# lcsc.net
KiCad netlist of a schematic drawn in EAGLE
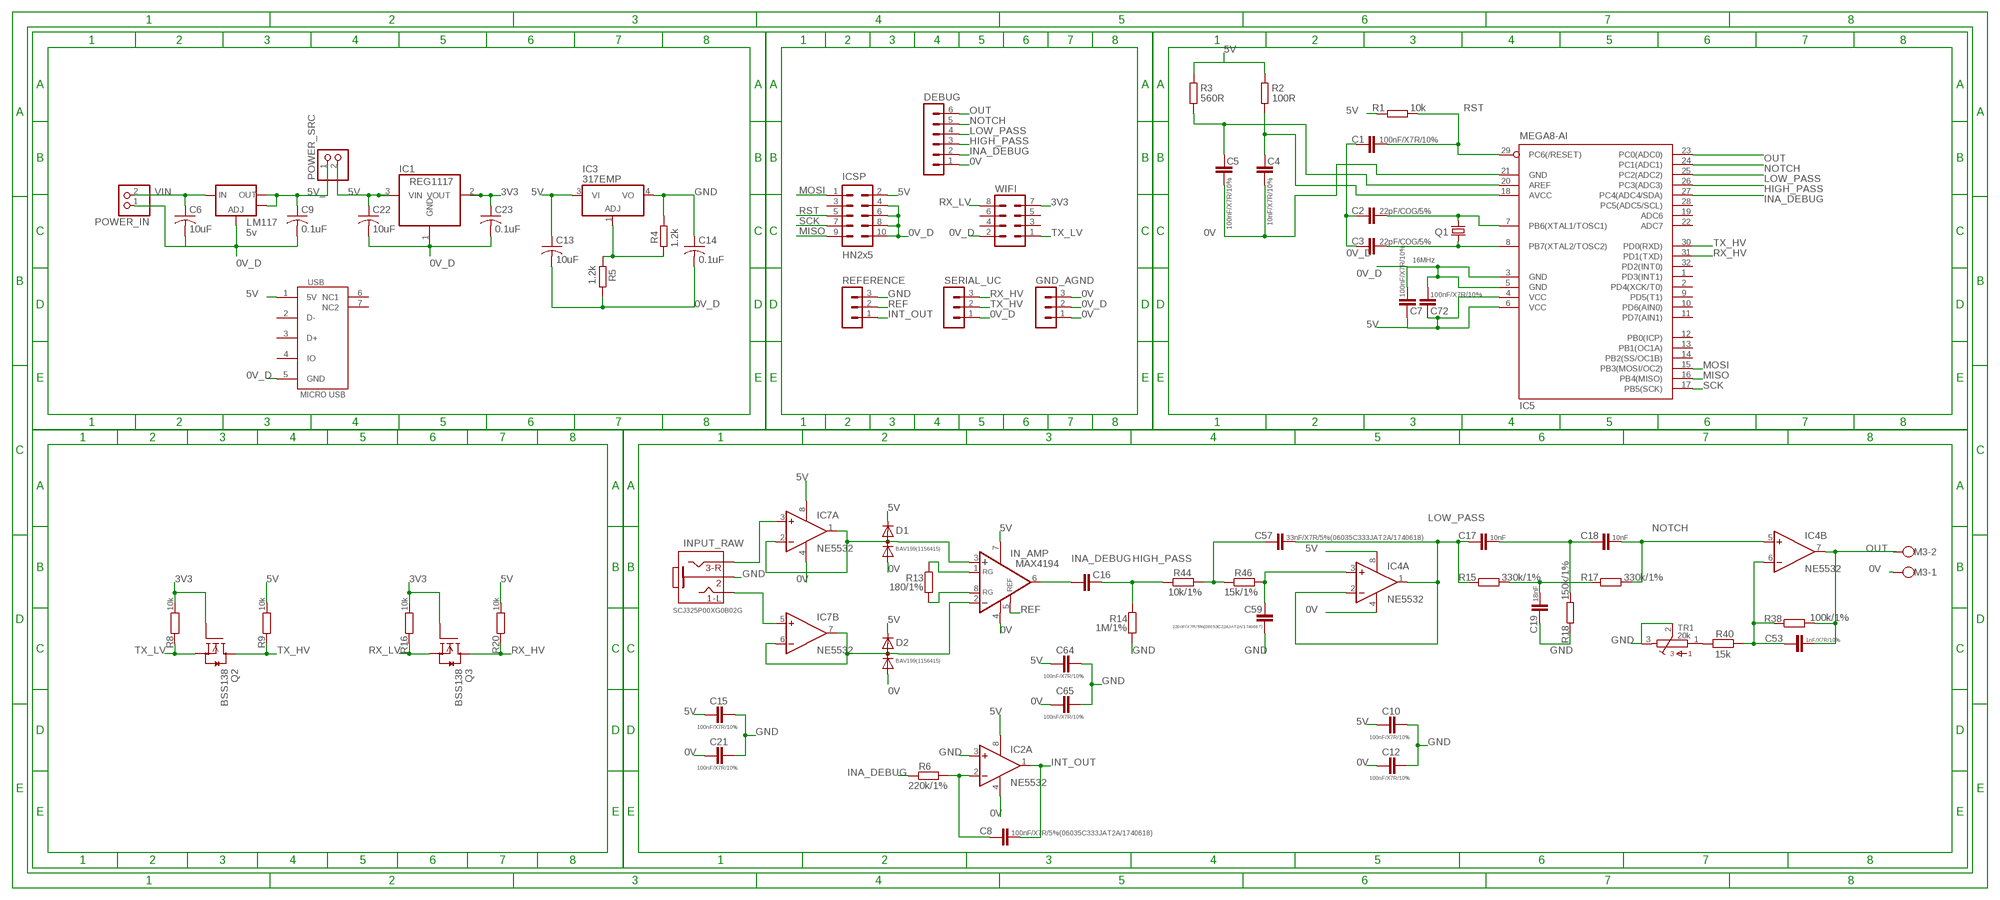
[diagram p0: schematic, sheet 1]

(export (version "E")
  (design (tool "Eeschema 10.0.6"))
  (components
    (comp (ref "C1")
      (value "100nF/X7R/10%")
      (footprint "eagle-import:C0603_DWS")
      (libsource (lib "eagle-import") (part "C-EUC0603_DWS"))
    )
    (comp (ref "C2")
      (value "22pF/COG/5%")
      (footprint "eagle-import:C0603_DWS")
      (libsource (lib "eagle-import") (part "C-EUC0603_DWS"))
    )
    (comp (ref "C3")
      (value "22pF/COG/5%")
      (footprint "eagle-import:C0603_DWS")
      (libsource (lib "eagle-import") (part "C-EUC0603_DWS"))
    )
    (comp (ref "C4")
      (value "10nF/X7R/10%")
      (footprint "eagle-import:C0603_DWS")
      (libsource (lib "eagle-import") (part "C-EUC0603_DWS"))
    )
    (comp (ref "C5")
      (value "100nF/X7R/10%")
      (footprint "eagle-import:C0603_DWS")
      (libsource (lib "eagle-import") (part "C-EUC0603_DWS"))
    )
    (comp (ref "C6")
      (value "10uF")
      (footprint "eagle-import:C0805")
      (libsource (lib "eagle-import") (part "C-USC0805"))
    )
    (comp (ref "C7")
      (value "100nF/X7R/10%")
      (footprint "eagle-import:C0603_DWS")
      (libsource (lib "eagle-import") (part "C-EUC0603_DWS"))
    )
    (comp (ref "C8")
      (value "100nF/X7R/5%(06035C333JAT2A/1740618)")
      (footprint "eagle-import:C0603_DWS")
      (libsource (lib "eagle-import") (part "C-EUC0603_DWS"))
    )
    (comp (ref "C9")
      (value "0.1uF")
      (footprint "eagle-import:C0805")
      (libsource (lib "eagle-import") (part "C-USC0805"))
    )
    (comp (ref "C10")
      (value "100nF/X7R/10%")
      (footprint "eagle-import:C0603_DWS")
      (libsource (lib "eagle-import") (part "C-EUC0603_DWS"))
    )
    (comp (ref "C12")
      (value "100nF/X7R/10%")
      (footprint "eagle-import:C0603_DWS")
      (libsource (lib "eagle-import") (part "C-EUC0603_DWS"))
    )
    (comp (ref "C13")
      (value "10uF")
      (footprint "eagle-import:C0805")
      (libsource (lib "eagle-import") (part "C-USC0805"))
    )
    (comp (ref "C14")
      (value "0.1uF")
      (footprint "eagle-import:C0805")
      (libsource (lib "eagle-import") (part "C-USC0805"))
    )
    (comp (ref "C15")
      (value "100nF/X7R/10%")
      (footprint "eagle-import:C0603_DWS")
      (libsource (lib "eagle-import") (part "C-EUC0603_DWS"))
    )
    (comp (ref "C16")
      (value "1uF/X5R/10%")
      (footprint "eagle-import:C0603_DWS")
      (libsource (lib "eagle-import") (part "C-EUC0603_DWS"))
    )
    (comp (ref "C17")
      (value "10nF")
      (footprint "eagle-import:C0603_DWS")
      (libsource (lib "eagle-import") (part "C-EUC0603_DWS"))
    )
    (comp (ref "C18")
      (value "10nF")
      (footprint "eagle-import:C0603_DWS")
      (libsource (lib "eagle-import") (part "C-EUC0603_DWS"))
    )
    (comp (ref "C19")
      (value "18nF")
      (footprint "eagle-import:C0603_DWS")
      (libsource (lib "eagle-import") (part "C-EUC0603_DWS"))
    )
    (comp (ref "C21")
      (value "100nF/X7R/10%")
      (footprint "eagle-import:C0603_DWS")
      (libsource (lib "eagle-import") (part "C-EUC0603_DWS"))
    )
    (comp (ref "C22")
      (value "10uF")
      (footprint "eagle-import:C0805")
      (libsource (lib "eagle-import") (part "C-USC0805"))
    )
    (comp (ref "C23")
      (value "0.1uF")
      (footprint "eagle-import:C0805")
      (libsource (lib "eagle-import") (part "C-USC0805"))
    )
    (comp (ref "C53")
      (value "1nF/X7R/10%")
      (footprint "eagle-import:C0603_DWS")
      (libsource (lib "eagle-import") (part "C-EUC0603_DWS"))
    )
    (comp (ref "C57")
      (value "33nF/X7R/5%(06035C333JAT2A/1740618)")
      (footprint "eagle-import:C0603_DWS")
      (libsource (lib "eagle-import") (part "C-EUC0603_DWS"))
    )
    (comp (ref "C59")
      (value "220nF/X7R/5%(08053C224JAT2A/1740667)")
      (footprint "eagle-import:C0805_5MIL_DWS")
      (libsource (lib "eagle-import") (part "C-EUC0805_5MIL_DWS"))
    )
    (comp (ref "C64")
      (value "100nF/X7R/10%")
      (footprint "eagle-import:C0603_DWS")
      (libsource (lib "eagle-import") (part "C-EUC0603_DWS"))
    )
    (comp (ref "C65")
      (value "100nF/X7R/10%")
      (footprint "eagle-import:C0603_DWS")
      (libsource (lib "eagle-import") (part "C-EUC0603_DWS"))
    )
    (comp (ref "C72")
      (value "100nF/X7R/10%")
      (footprint "eagle-import:C0603_DWS")
      (libsource (lib "eagle-import") (part "C-EUC0603_DWS"))
    )
    (comp (ref "D1")
      (value "BAV199(1156415)")
      (footprint "eagle-import:SOT23C(BAT54S)")
      (libsource (lib "eagle-import") (part "DIODE_AC-AC_"))
    )
    (comp (ref "D2")
      (value "BAV199(1156415)")
      (footprint "eagle-import:SOT23C(BAT54S)")
      (libsource (lib "eagle-import") (part "DIODE_AC-AC_"))
    )
    (comp (ref "DEBUG")
      (value "MA06-1")
      (footprint "eagle-import:MA06-1")
      (libsource (lib "eagle-import") (part "MA06-1"))
    )
    (comp (ref "GND_AGND")
      (value "MA03-1")
      (footprint "eagle-import:MA03-1")
      (libsource (lib "eagle-import") (part "MA03-1"))
    )
    (comp (ref "IC1")
      (value "REG1117")
      (footprint "eagle-import:SOT223")
      (libsource (lib "eagle-import") (part "REG1117"))
    )
    (comp (ref "IC2")
      (value "NE5532")
      (footprint "eagle-import:SO08")
      (libsource (lib "eagle-import") (part "LMV358?M"))
    )
    (comp (ref "IC3")
      (value "317EMP")
      (footprint "eagle-import:SOT223")
      (libsource (lib "eagle-import") (part "317EMP"))
    )
    (comp (ref "IC4")
      (value "NE5532")
      (footprint "eagle-import:SO08")
      (libsource (lib "eagle-import") (part "LMV358?M"))
    )
    (comp (ref "IC5")
      (value "MEGA8-AI")
      (footprint "eagle-import:TQFP32-08")
      (fields (field (name "MPN") "ATMEGA8-16AU"))
      (libsource (lib "eagle-import") (part "MEGA8-AI"))
    )
    (comp (ref "IC7")
      (value "NE5532")
      (footprint "eagle-import:SO08")
      (libsource (lib "eagle-import") (part "LMV358?M"))
    )
    (comp (ref "ICSP")
      (value "HN2x5")
      (footprint "eagle-import:ML10_NEW")
      (libsource (lib "eagle-import") (part "ML10ML10_NEW"))
    )
    (comp (ref "INPUT_RAW")
      (value "SCJ325P00XG0B02G")
      (footprint "eagle-import:PHONE_JACK-SMD")
      (libsource (lib "eagle-import") (part "JACK-3PINPHONE_JACK-SMD"))
    )
    (comp (ref "IN_AMP")
      (value "MAX4194")
      (footprint "eagle-import:SOIC8")
      (fields (field (name "MPN") "LT1168ACS8"))
      (libsource (lib "eagle-import") (part "LT1168S8AC"))
    )
    (comp (ref "LM117")
      (value "5v")
      (footprint "eagle-import:SOT223")
      (libsource (lib "eagle-import") (part "V_REG_LM1117SOT223"))
    )
    (comp (ref "M3")
      (value "W237-102")
      (footprint "eagle-import:W237-102")
      (fields (field (name "MPN") "237-102"))
      (libsource (lib "eagle-import") (part "W237-102"))
    )
    (comp (ref "POWER_IN")
      (value "PINHD-1X2")
      (footprint "eagle-import:1X02")
      (libsource (lib "eagle-import") (part "PINHD-1X2"))
    )
    (comp (ref "POWER_SRC")
      (value "PINHD-1X2")
      (footprint "eagle-import:1X02")
      (libsource (lib "eagle-import") (part "PINHD-1X2"))
    )
    (comp (ref "Q1")
      (value "16MHz")
      (footprint "eagle-import:HC49_SMD2_THIN")
      (libsource (lib "eagle-import") (part "HC49/S1"))
    )
    (comp (ref "Q2")
      (value "BSS138")
      (footprint "eagle-import:SOT23")
      (libsource (lib "eagle-import") (part "BSS138"))
    )
    (comp (ref "Q3")
      (value "BSS138")
      (footprint "eagle-import:SOT23")
      (libsource (lib "eagle-import") (part "BSS138"))
    )
    (comp (ref "R1")
      (value "10k")
      (footprint "eagle-import:R0603_5MIL_DWS")
      (libsource (lib "eagle-import") (part "R-EU_R0603_5MIL_DWS"))
    )
    (comp (ref "R2")
      (value "100R")
      (footprint "eagle-import:R0603_5MIL_DWS")
      (libsource (lib "eagle-import") (part "R-EU_R0603_5MIL_DWS"))
    )
    (comp (ref "R3")
      (value "560R")
      (footprint "eagle-import:R0603_5MIL_DWS")
      (libsource (lib "eagle-import") (part "R-EU_R0603_5MIL_DWS"))
    )
    (comp (ref "R4")
      (value "1.2k")
      (footprint "eagle-import:R0603_5MIL_DWS")
      (libsource (lib "eagle-import") (part "R-EU_R0603_5MIL_DWS"))
    )
    (comp (ref "R5")
      (value "1.2k")
      (footprint "eagle-import:R0603_5MIL_DWS")
      (libsource (lib "eagle-import") (part "R-EU_R0603_5MIL_DWS"))
    )
    (comp (ref "R6")
      (value "220k/1%")
      (footprint "eagle-import:R0603_5MIL_DWS")
      (libsource (lib "eagle-import") (part "R-EU_R0603_5MIL_DWS"))
    )
    (comp (ref "R8")
      (value "10k")
      (footprint "eagle-import:R0603_5MIL_DWS")
      (libsource (lib "eagle-import") (part "R-EU_R0603_5MIL_DWS"))
    )
    (comp (ref "R9")
      (value "10k")
      (footprint "eagle-import:R0603_5MIL_DWS")
      (libsource (lib "eagle-import") (part "R-EU_R0603_5MIL_DWS"))
    )
    (comp (ref "R13")
      (value "180/1%")
      (footprint "eagle-import:R0603_5MIL_DWS")
      (libsource (lib "eagle-import") (part "R-EU_R0603_5MIL_DWS"))
    )
    (comp (ref "R14")
      (value "1M/1%")
      (footprint "eagle-import:R0603_5MIL_DWS")
      (libsource (lib "eagle-import") (part "R-EU_R0603_5MIL_DWS"))
    )
    (comp (ref "R15")
      (value "330k/1%")
      (footprint "eagle-import:R0603_5MIL_DWS")
      (libsource (lib "eagle-import") (part "R-EU_R0603_5MIL_DWS"))
    )
    (comp (ref "R16")
      (value "10k")
      (footprint "eagle-import:R0603_5MIL_DWS")
      (libsource (lib "eagle-import") (part "R-EU_R0603_5MIL_DWS"))
    )
    (comp (ref "R17")
      (value "330k/1%")
      (footprint "eagle-import:R0603_5MIL_DWS")
      (libsource (lib "eagle-import") (part "R-EU_R0603_5MIL_DWS"))
    )
    (comp (ref "R18")
      (value "150k/1%")
      (footprint "eagle-import:R0603_5MIL_DWS")
      (libsource (lib "eagle-import") (part "R-EU_R0603_5MIL_DWS"))
    )
    (comp (ref "R20")
      (value "10k")
      (footprint "eagle-import:R0603_5MIL_DWS")
      (libsource (lib "eagle-import") (part "R-EU_R0603_5MIL_DWS"))
    )
    (comp (ref "R38")
      (value "100k/1%")
      (footprint "eagle-import:R0603_5MIL_DWS")
      (libsource (lib "eagle-import") (part "R-EU_R0603_5MIL_DWS"))
    )
    (comp (ref "R40")
      (value "15k")
      (footprint "eagle-import:R0603_5MIL_DWS")
      (libsource (lib "eagle-import") (part "R-EU_R0603_5MIL_DWS"))
    )
    (comp (ref "R44")
      (value "10k/1%")
      (footprint "eagle-import:R0603_5MIL_DWS")
      (libsource (lib "eagle-import") (part "R-EU_R0603_5MIL_DWS"))
    )
    (comp (ref "R46")
      (value "15k/1%")
      (footprint "eagle-import:R0603_5MIL_DWS")
      (libsource (lib "eagle-import") (part "R-EU_R0603_5MIL_DWS"))
    )
    (comp (ref "REFERENCE")
      (value "MA03-1")
      (footprint "eagle-import:MA03-1")
      (libsource (lib "eagle-import") (part "MA03-1"))
    )
    (comp (ref "SERIAL_UC")
      (value "MA03-1")
      (footprint "eagle-import:MA03-1")
      (libsource (lib "eagle-import") (part "MA03-1"))
    )
    (comp (ref "TR1")
      (value "20k")
      (footprint "eagle-import:S64Y")
      (libsource (lib "eagle-import") (part "S64Y"))
    )
    (comp (ref "USB")
      (value "MICRO_USB")
      (footprint "eagle-import:MICRO_USB")
      (libsource (lib "eagle-import") (part "MICRO_USB"))
    )
    (comp (ref "WIFI")
      (value "MA04-2")
      (footprint "eagle-import:MA04-2")
      (libsource (lib "eagle-import") (part "MA04-2"))
    )
  )
  (nets
    (net (code "1") (name "/0V") (class "Default")
      (node (ref "C12") (pin "1") (pinfunction "1_1") (pintype "passive"))
      (node (ref "C21") (pin "1") (pinfunction "1_1") (pintype "passive"))
      (node (ref "C4") (pin "2") (pinfunction "2_2") (pintype "passive"))
      (node (ref "C5") (pin "2") (pinfunction "2_2") (pintype "passive"))
      (node (ref "C65") (pin "1") (pinfunction "1_1") (pintype "passive"))
      (node (ref "D1") (pin "1") (pinfunction "A_1") (pintype "passive"))
      (node (ref "D2") (pin "1") (pinfunction "A_1") (pintype "passive"))
      (node (ref "DEBUG") (pin "1") (pinfunction "1_1") (pintype "passive"))
      (node (ref "GND_AGND") (pin "1") (pinfunction "1_1") (pintype "passive"))
      (node (ref "GND_AGND") (pin "3") (pinfunction "3_3") (pintype "passive"))
      (node (ref "IC2") (pin "4") (pinfunction "V-_4") (pintype "power_in"))
      (node (ref "IC4") (pin "4") (pinfunction "V-_4") (pintype "power_in"))
      (node (ref "IC5") (pin "21") (pinfunction "GND_21") (pintype "power_in"))
      (node (ref "IC7") (pin "4") (pinfunction "V-_4") (pintype "power_in"))
      (node (ref "IN_AMP") (pin "4") (pinfunction "V-_4") (pintype "power_in"))
      (node (ref "M3") (pin "1") (pinfunction "KL_1") (pintype "passive"))
    )
    (net (code "2") (name "/0V_D") (class "Default")
      (node (ref "C1") (pin "2") (pinfunction "2_2") (pintype "passive"))
      (node (ref "C13") (pin "2") (pinfunction "2_2") (pintype "passive"))
      (node (ref "C14") (pin "2") (pinfunction "2_2") (pintype "passive"))
      (node (ref "C2") (pin "2") (pinfunction "2_2") (pintype "passive"))
      (node (ref "C22") (pin "2") (pinfunction "2_2") (pintype "passive"))
      (node (ref "C23") (pin "2") (pinfunction "2_2") (pintype "passive"))
      (node (ref "C3") (pin "2") (pinfunction "2_2") (pintype "passive"))
      (node (ref "C6") (pin "2") (pinfunction "2_2") (pintype "passive"))
      (node (ref "C7") (pin "2") (pinfunction "2_2") (pintype "passive"))
      (node (ref "C72") (pin "2") (pinfunction "2_2") (pintype "passive"))
      (node (ref "C9") (pin "2") (pinfunction "2_2") (pintype "passive"))
      (node (ref "GND_AGND") (pin "2") (pinfunction "2_2") (pintype "passive"))
      (node (ref "IC1") (pin "1") (pinfunction "GND_1") (pintype "power_in"))
      (node (ref "IC5") (pin "3") (pinfunction "GND_3") (pintype "power_in"))
      (node (ref "IC5") (pin "5") (pinfunction "GND_5") (pintype "power_in"))
      (node (ref "ICSP") (pin "10") (pinfunction "10_10") (pintype "passive"))
      (node (ref "ICSP") (pin "4") (pinfunction "4_4") (pintype "passive"))
      (node (ref "ICSP") (pin "6") (pinfunction "6_6") (pintype "passive"))
      (node (ref "ICSP") (pin "8") (pinfunction "8_8") (pintype "passive"))
      (node (ref "LM117") (pin "1") (pinfunction "ADJ_1") (pintype "input"))
      (node (ref "POWER_IN") (pin "1") (pinfunction "1_1") (pintype "passive"))
      (node (ref "R5") (pin "1") (pinfunction "1_1") (pintype "passive"))
      (node (ref "SERIAL_UC") (pin "1") (pinfunction "1_1") (pintype "passive"))
      (node (ref "USB") (pin "5") (pinfunction "GND_5") (pintype "bidirectional"))
      (node (ref "WIFI") (pin "2") (pinfunction "2_2") (pintype "passive"))
    )
    (net (code "3") (name "/3V3") (class "Default")
      (node (ref "C23") (pin "1") (pinfunction "1_1") (pintype "passive"))
      (node (ref "IC1") (pin "2") (pinfunction "VOUT_2") (pintype "output"))
      (node (ref "Q2") (pin "1") (pinfunction "G_1") (pintype "passive"))
      (node (ref "Q3") (pin "1") (pinfunction "G_1") (pintype "passive"))
      (node (ref "R16") (pin "2") (pinfunction "2_2") (pintype "passive"))
      (node (ref "R8") (pin "2") (pinfunction "2_2") (pintype "passive"))
      (node (ref "WIFI") (pin "7") (pinfunction "7_7") (pintype "passive"))
    )
    (net (code "4") (name "/5V") (class "Default")
      (node (ref "C10") (pin "1") (pinfunction "1_1") (pintype "passive"))
      (node (ref "C13") (pin "1") (pinfunction "1_1") (pintype "passive"))
      (node (ref "C15") (pin "1") (pinfunction "1_1") (pintype "passive"))
      (node (ref "C22") (pin "1") (pinfunction "1_1") (pintype "passive"))
      (node (ref "C64") (pin "1") (pinfunction "1_1") (pintype "passive"))
      (node (ref "C7") (pin "1") (pinfunction "1_1") (pintype "passive"))
      (node (ref "C72") (pin "1") (pinfunction "1_1") (pintype "passive"))
      (node (ref "D1") (pin "2") (pinfunction "K_2") (pintype "passive"))
      (node (ref "D2") (pin "2") (pinfunction "K_2") (pintype "passive"))
      (node (ref "IC1") (pin "3") (pinfunction "VIN_3") (pintype "input"))
      (node (ref "IC2") (pin "8") (pinfunction "V+_8") (pintype "power_in"))
      (node (ref "IC3") (pin "3") (pinfunction "VI_3") (pintype "input"))
      (node (ref "IC4") (pin "8") (pinfunction "V+_8") (pintype "power_in"))
      (node (ref "IC5") (pin "4") (pinfunction "VCC_4") (pintype "power_in"))
      (node (ref "IC5") (pin "6") (pinfunction "VCC_6") (pintype "power_in"))
      (node (ref "IC7") (pin "8") (pinfunction "V+_8") (pintype "power_in"))
      (node (ref "ICSP") (pin "2") (pinfunction "2_2") (pintype "passive"))
      (node (ref "IN_AMP") (pin "7") (pinfunction "V+_7") (pintype "power_in"))
      (node (ref "POWER_SRC") (pin "2") (pinfunction "2_2") (pintype "passive"))
      (node (ref "R1") (pin "1") (pinfunction "1_1") (pintype "passive"))
      (node (ref "R2") (pin "2") (pinfunction "2_2") (pintype "passive"))
      (node (ref "R20") (pin "2") (pinfunction "2_2") (pintype "passive"))
      (node (ref "R3") (pin "2") (pinfunction "2_2") (pintype "passive"))
      (node (ref "R9") (pin "2") (pinfunction "2_2") (pintype "passive"))
      (node (ref "USB") (pin "1") (pinfunction "5V_1") (pintype "bidirectional"))
    )
    (net (code "5") (name "/5V_") (class "Default")
      (node (ref "C9") (pin "1") (pinfunction "1_1") (pintype "passive"))
      (node (ref "LM117") (pin "2") (pinfunction "OUT_2") (pintype "output"))
      (node (ref "LM117") (pin "4") (pinfunction "OUT_4") (pintype "output"))
      (node (ref "POWER_SRC") (pin "1") (pinfunction "1_1") (pintype "passive"))
    )
    (net (code "6") (name "/GND") (class "Default")
      (node (ref "C10") (pin "2") (pinfunction "2_2") (pintype "passive"))
      (node (ref "C12") (pin "2") (pinfunction "2_2") (pintype "passive"))
      (node (ref "C14") (pin "1") (pinfunction "1_1") (pintype "passive"))
      (node (ref "C15") (pin "2") (pinfunction "2_2") (pintype "passive"))
      (node (ref "C19") (pin "1") (pinfunction "1_1") (pintype "passive"))
      (node (ref "C21") (pin "2") (pinfunction "2_2") (pintype "passive"))
      (node (ref "C59") (pin "2") (pinfunction "2_2") (pintype "passive"))
      (node (ref "C64") (pin "2") (pinfunction "2_2") (pintype "passive"))
      (node (ref "C65") (pin "2") (pinfunction "2_2") (pintype "passive"))
      (node (ref "IC2") (pin "3") (pinfunction "+IN_3") (pintype "input"))
      (node (ref "IC3") (pin "4") (pinfunction "VO_4") (pintype "passive"))
      (node (ref "INPUT_RAW") (pin "1") (pinfunction "2_1") (pintype "input"))
      (node (ref "R14") (pin "2") (pinfunction "2_2") (pintype "passive"))
      (node (ref "R18") (pin "1") (pinfunction "1_1") (pintype "passive"))
      (node (ref "R4") (pin "1") (pinfunction "1_1") (pintype "passive"))
      (node (ref "REFERENCE") (pin "3") (pinfunction "3_3") (pintype "passive"))
      (node (ref "TR1") (pin "2") (pinfunction "2_2") (pintype "passive"))
      (node (ref "TR1") (pin "3") (pinfunction "3_3") (pintype "passive"))
    )
    (net (code "7") (name "/HIGH_PASS") (class "Default")
      (node (ref "C16") (pin "2") (pinfunction "2_2") (pintype "passive"))
      (node (ref "DEBUG") (pin "3") (pinfunction "3_3") (pintype "passive"))
      (node (ref "IC5") (pin "26") (pinfunction "PC3(ADC3)_26") (pintype "bidirectional"))
      (node (ref "R14") (pin "1") (pinfunction "1_1") (pintype "passive"))
      (node (ref "R44") (pin "1") (pinfunction "1_1") (pintype "passive"))
    )
    (net (code "8") (name "/INA_DEBUG") (class "Default")
      (node (ref "C16") (pin "1") (pinfunction "1_1") (pintype "passive"))
      (node (ref "DEBUG") (pin "2") (pinfunction "2_2") (pintype "passive"))
      (node (ref "IC5") (pin "27") (pinfunction "PC4(ADC4/SDA)_27") (pintype "bidirectional"))
      (node (ref "IN_AMP") (pin "6") (pinfunction "OUT_6") (pintype "output"))
      (node (ref "R6") (pin "1") (pinfunction "1_1") (pintype "passive"))
    )
    (net (code "9") (name "/INT_OUT") (class "Default")
      (node (ref "C8") (pin "2") (pinfunction "2_2") (pintype "passive"))
      (node (ref "IC2") (pin "1") (pinfunction "OUT_1") (pintype "output"))
      (node (ref "REFERENCE") (pin "1") (pinfunction "1_1") (pintype "passive"))
    )
    (net (code "10") (name "/LOW_PASS") (class "Default")
      (node (ref "C17") (pin "1") (pinfunction "1_1") (pintype "passive"))
      (node (ref "C57") (pin "2") (pinfunction "2_2") (pintype "passive"))
      (node (ref "DEBUG") (pin "4") (pinfunction "4_4") (pintype "passive"))
      (node (ref "IC4") (pin "1") (pinfunction "OUT_1") (pintype "output"))
      (node (ref "IC4") (pin "2") (pinfunction "-IN_2") (pintype "input"))
      (node (ref "IC5") (pin "25") (pinfunction "PC2(ADC2)_25") (pintype "bidirectional"))
      (node (ref "R15") (pin "1") (pinfunction "1_1") (pintype "passive"))
    )
    (net (code "11") (name "/MISO") (class "Default")
      (node (ref "IC5") (pin "16") (pinfunction "PB4(MISO)_16") (pintype "bidirectional"))
      (node (ref "ICSP") (pin "9") (pinfunction "9_9") (pintype "passive"))
    )
    (net (code "12") (name "/MOSI") (class "Default")
      (node (ref "IC5") (pin "15") (pinfunction "PB3(MOSI/OC2)_15") (pintype "bidirectional"))
      (node (ref "ICSP") (pin "1") (pinfunction "1_1") (pintype "passive"))
    )
    (net (code "13") (name "/NOTCH") (class "Default")
      (node (ref "C18") (pin "2") (pinfunction "2_2") (pintype "passive"))
      (node (ref "DEBUG") (pin "5") (pinfunction "5_5") (pintype "passive"))
      (node (ref "IC4") (pin "5") (pinfunction "+IN_5") (pintype "input"))
      (node (ref "IC5") (pin "24") (pinfunction "PC1(ADC1)_24") (pintype "bidirectional"))
      (node (ref "R17") (pin "2") (pinfunction "2_2") (pintype "passive"))
    )
    (net (code "14") (name "/OUT") (class "Default")
      (node (ref "C53") (pin "2") (pinfunction "2_2") (pintype "passive"))
      (node (ref "DEBUG") (pin "6") (pinfunction "6_6") (pintype "passive"))
      (node (ref "IC4") (pin "7") (pinfunction "OUT_7") (pintype "output"))
      (node (ref "IC5") (pin "23") (pinfunction "PC0(ADC0)_23") (pintype "bidirectional"))
      (node (ref "M3") (pin "2") (pinfunction "KL_2") (pintype "passive"))
      (node (ref "R38") (pin "2") (pinfunction "2_2") (pintype "passive"))
    )
    (net (code "15") (name "/REF") (class "Default")
      (node (ref "IN_AMP") (pin "5") (pinfunction "REF_5") (pintype "input"))
      (node (ref "REFERENCE") (pin "2") (pinfunction "2_2") (pintype "passive"))
    )
    (net (code "16") (name "/RST") (class "Default")
      (node (ref "C1") (pin "1") (pinfunction "1_1") (pintype "passive"))
      (node (ref "IC5") (pin "29") (pinfunction "PC6(/RESET)_29") (pintype "bidirectional"))
      (node (ref "ICSP") (pin "5") (pinfunction "5_5") (pintype "passive"))
      (node (ref "R1") (pin "2") (pinfunction "2_2") (pintype "passive"))
    )
    (net (code "17") (name "/RX_HV") (class "Default")
      (node (ref "IC5") (pin "31") (pinfunction "PD1(TXD)_31") (pintype "bidirectional"))
      (node (ref "Q3") (pin "3") (pinfunction "D_3") (pintype "passive"))
      (node (ref "R20") (pin "1") (pinfunction "1_1") (pintype "passive"))
      (node (ref "SERIAL_UC") (pin "3") (pinfunction "3_3") (pintype "passive"))
    )
    (net (code "18") (name "/RX_LV") (class "Default")
      (node (ref "Q3") (pin "2") (pinfunction "S_2") (pintype "passive"))
      (node (ref "R16") (pin "1") (pinfunction "1_1") (pintype "passive"))
      (node (ref "WIFI") (pin "8") (pinfunction "8_8") (pintype "passive"))
    )
    (net (code "19") (name "/SCK") (class "Default")
      (node (ref "IC5") (pin "17") (pinfunction "PB5(SCK)_17") (pintype "bidirectional"))
      (node (ref "ICSP") (pin "7") (pinfunction "7_7") (pintype "passive"))
    )
    (net (code "20") (name "/TX_HV") (class "Default")
      (node (ref "IC5") (pin "30") (pinfunction "PD0(RXD)_30") (pintype "bidirectional"))
      (node (ref "Q2") (pin "3") (pinfunction "D_3") (pintype "passive"))
      (node (ref "R9") (pin "1") (pinfunction "1_1") (pintype "passive"))
      (node (ref "SERIAL_UC") (pin "2") (pinfunction "2_2") (pintype "passive"))
    )
    (net (code "21") (name "/TX_LV") (class "Default")
      (node (ref "Q2") (pin "2") (pinfunction "S_2") (pintype "passive"))
      (node (ref "R8") (pin "1") (pinfunction "1_1") (pintype "passive"))
      (node (ref "WIFI") (pin "1") (pinfunction "1_1") (pintype "passive"))
    )
    (net (code "22") (name "/VIN") (class "Default")
      (node (ref "C6") (pin "1") (pinfunction "1_1") (pintype "passive"))
      (node (ref "LM117") (pin "3") (pinfunction "IN_3") (pintype "input"))
      (node (ref "POWER_IN") (pin "2") (pinfunction "2_2") (pintype "passive"))
    )
    (net (code "23") (name "Net-(C17-Pad2)") (class "Default")
      (node (ref "C17") (pin "2") (pinfunction "2_2") (pintype "passive"))
      (node (ref "C18") (pin "1") (pinfunction "1_1") (pintype "passive"))
      (node (ref "R18") (pin "2") (pinfunction "2_2") (pintype "passive"))
    )
    (net (code "24") (name "Net-(C19-Pad2)") (class "Default")
      (node (ref "C19") (pin "2") (pinfunction "2_2") (pintype "passive"))
      (node (ref "R15") (pin "2") (pinfunction "2_2") (pintype "passive"))
      (node (ref "R17") (pin "1") (pinfunction "1_1") (pintype "passive"))
    )
    (net (code "25") (name "Net-(C57-Pad1)") (class "Default")
      (node (ref "C57") (pin "1") (pinfunction "1_1") (pintype "passive"))
      (node (ref "R44") (pin "2") (pinfunction "2_2") (pintype "passive"))
      (node (ref "R46") (pin "1") (pinfunction "1_1") (pintype "passive"))
    )
    (net (code "26") (name "Net-(D1-AK)") (class "Default")
      (node (ref "D1") (pin "3") (pinfunction "AK_3") (pintype "passive"))
      (node (ref "IC7") (pin "1") (pinfunction "OUT_1") (pintype "output"))
      (node (ref "IC7") (pin "2") (pinfunction "-IN_2") (pintype "input"))
      (node (ref "IN_AMP") (pin "3") (pinfunction "+IN_3") (pintype "input"))
    )
    (net (code "27") (name "Net-(D2-AK)") (class "Default")
      (node (ref "D2") (pin "3") (pinfunction "AK_3") (pintype "passive"))
      (node (ref "IC7") (pin "6") (pinfunction "-IN_6") (pintype "input"))
      (node (ref "IC7") (pin "7") (pinfunction "OUT_7") (pintype "output"))
      (node (ref "IN_AMP") (pin "2") (pinfunction "-IN_2") (pintype "input"))
    )
    (net (code "28") (name "Net-(IC2A--IN)") (class "Default")
      (node (ref "C8") (pin "1") (pinfunction "1_1") (pintype "passive"))
      (node (ref "IC2") (pin "2") (pinfunction "-IN_2") (pintype "input"))
      (node (ref "R6") (pin "2") (pinfunction "2_2") (pintype "passive"))
    )
    (net (code "29") (name "Net-(IC3-ADJ)") (class "Default")
      (node (ref "IC3") (pin "1") (pinfunction "ADJ_1") (pintype "input"))
      (node (ref "R4") (pin "2") (pinfunction "2_2") (pintype "passive"))
      (node (ref "R5") (pin "2") (pinfunction "2_2") (pintype "passive"))
    )
    (net (code "30") (name "Net-(IC4A-+IN)") (class "Default")
      (node (ref "C59") (pin "1") (pinfunction "1_1") (pintype "passive"))
      (node (ref "IC4") (pin "3") (pinfunction "+IN_3") (pintype "input"))
      (node (ref "R46") (pin "2") (pinfunction "2_2") (pintype "passive"))
    )
    (net (code "31") (name "Net-(IC4B--IN)") (class "Default")
      (node (ref "C53") (pin "1") (pinfunction "1_1") (pintype "passive"))
      (node (ref "IC4") (pin "6") (pinfunction "-IN_6") (pintype "input"))
      (node (ref "R38") (pin "1") (pinfunction "1_1") (pintype "passive"))
      (node (ref "R40") (pin "1") (pinfunction "1_1") (pintype "passive"))
    )
    (net (code "32") (name "Net-(IC5-AREF)") (class "Default")
      (node (ref "C5") (pin "1") (pinfunction "1_1") (pintype "passive"))
      (node (ref "IC5") (pin "20") (pinfunction "AREF_20") (pintype "passive"))
      (node (ref "R3") (pin "1") (pinfunction "1_1") (pintype "passive"))
    )
    (net (code "33") (name "Net-(IC5-AVCC)") (class "Default")
      (node (ref "C4") (pin "1") (pinfunction "1_1") (pintype "passive"))
      (node (ref "IC5") (pin "18") (pinfunction "AVCC_18") (pintype "power_in"))
      (node (ref "R2") (pin "1") (pinfunction "1_1") (pintype "passive"))
    )
    (net (code "34") (name "Net-(IC5-PB6(XTAL1{slash}TOSC1))") (class "Default")
      (node (ref "C2") (pin "1") (pinfunction "1_1") (pintype "passive"))
      (node (ref "IC5") (pin "7") (pinfunction "PB6(XTAL1/TOSC1)_7") (pintype "bidirectional"))
      (node (ref "Q1") (pin "1") (pinfunction "1_1") (pintype "passive"))
    )
    (net (code "35") (name "Net-(IC5-PB7(XTAL2{slash}TOSC2))") (class "Default")
      (node (ref "C3") (pin "1") (pinfunction "1_1") (pintype "passive"))
      (node (ref "IC5") (pin "8") (pinfunction "PB7(XTAL2/TOSC2)_8") (pintype "bidirectional"))
      (node (ref "Q1") (pin "2") (pinfunction "2_2") (pintype "passive"))
    )
    (net (code "36") (name "Net-(IC7A-+IN)") (class "Default")
      (node (ref "IC7") (pin "3") (pinfunction "+IN_3") (pintype "input"))
      (node (ref "INPUT_RAW") (pin "2") (pinfunction "3_2") (pintype "bidirectional"))
    )
    (net (code "37") (name "Net-(IC7B-+IN)") (class "Default")
      (node (ref "IC7") (pin "5") (pinfunction "+IN_5") (pintype "input"))
      (node (ref "INPUT_RAW") (pin "5") (pinfunction "1_5") (pintype "bidirectional"))
    )
    (net (code "38") (name "Net-(IN_AMP-RG-Pad1)") (class "Default")
      (node (ref "IN_AMP") (pin "1") (pinfunction "RG_1") (pintype "input"))
      (node (ref "R13") (pin "1") (pinfunction "1_1") (pintype "passive"))
    )
    (net (code "39") (name "Net-(IN_AMP-RG-Pad8)") (class "Default")
      (node (ref "IN_AMP") (pin "8") (pinfunction "RG_8") (pintype "input"))
      (node (ref "R13") (pin "2") (pinfunction "2_2") (pintype "passive"))
    )
    (net (code "40") (name "Net-(R40-Pad2)") (class "Default")
      (node (ref "R40") (pin "2") (pinfunction "2_2") (pintype "passive"))
      (node (ref "TR1") (pin "1") (pinfunction "1_1") (pintype "passive"))
    )
    (net (code "41") (name "unconnected-(IC5-ADC6-Pad19)") (class "Default")
      (node (ref "IC5") (pin "19") (pinfunction "ADC6_19") (pintype "bidirectional"))
    )
    (net (code "42") (name "unconnected-(IC5-ADC7-Pad22)") (class "Default")
      (node (ref "IC5") (pin "22") (pinfunction "ADC7_22") (pintype "bidirectional"))
    )
    (net (code "43") (name "unconnected-(IC5-PB0(ICP)-Pad12)") (class "Default")
      (node (ref "IC5") (pin "12") (pinfunction "PB0(ICP)_12") (pintype "bidirectional"))
    )
    (net (code "44") (name "unconnected-(IC5-PB1(OC1A)-Pad13)") (class "Default")
      (node (ref "IC5") (pin "13") (pinfunction "PB1(OC1A)_13") (pintype "bidirectional"))
    )
    (net (code "45") (name "unconnected-(IC5-PB2(SS{slash}OC1B)-Pad14)") (class "Default")
      (node (ref "IC5") (pin "14") (pinfunction "PB2(SS/OC1B)_14") (pintype "bidirectional"))
    )
    (net (code "46") (name "unconnected-(IC5-PC5(ADC5{slash}SCL)-Pad28)") (class "Default")
      (node (ref "IC5") (pin "28") (pinfunction "PC5(ADC5/SCL)_28") (pintype "bidirectional"))
    )
    (net (code "47") (name "unconnected-(IC5-PD2(INT0)-Pad32)") (class "Default")
      (node (ref "IC5") (pin "32") (pinfunction "PD2(INT0)_32") (pintype "bidirectional"))
    )
    (net (code "48") (name "unconnected-(IC5-PD3(INT1)-Pad1)") (class "Default")
      (node (ref "IC5") (pin "1") (pinfunction "PD3(INT1)_1") (pintype "bidirectional"))
    )
    (net (code "49") (name "unconnected-(IC5-PD4(XCK{slash}T0)-Pad2)") (class "Default")
      (node (ref "IC5") (pin "2") (pinfunction "PD4(XCK/T0)_2") (pintype "bidirectional"))
    )
    (net (code "50") (name "unconnected-(IC5-PD5(T1)-Pad9)") (class "Default")
      (node (ref "IC5") (pin "9") (pinfunction "PD5(T1)_9") (pintype "bidirectional"))
    )
    (net (code "51") (name "unconnected-(IC5-PD6(AIN0)-Pad10)") (class "Default")
      (node (ref "IC5") (pin "10") (pinfunction "PD6(AIN0)_10") (pintype "bidirectional"))
    )
    (net (code "52") (name "unconnected-(IC5-PD7(AIN1)-Pad11)") (class "Default")
      (node (ref "IC5") (pin "11") (pinfunction "PD7(AIN1)_11") (pintype "bidirectional"))
    )
    (net (code "53") (name "unconnected-(ICSP-Pad3)") (class "Default")
      (node (ref "ICSP") (pin "3") (pinfunction "3_3") (pintype "passive"))
    )
    (net (code "54") (name "unconnected-(USB-D+-Pad3)") (class "Default")
      (node (ref "USB") (pin "3") (pinfunction "D+_3") (pintype "bidirectional"))
    )
    (net (code "55") (name "unconnected-(USB-D--Pad2)") (class "Default")
      (node (ref "USB") (pin "2") (pinfunction "D-_2") (pintype "bidirectional"))
    )
    (net (code "56") (name "unconnected-(USB-IO-Pad4)") (class "Default")
      (node (ref "USB") (pin "4") (pinfunction "IO_4") (pintype "bidirectional"))
    )
    (net (code "57") (name "unconnected-(USB-NC1-Pad6)") (class "Default")
      (node (ref "USB") (pin "6") (pinfunction "NC1_6") (pintype "bidirectional"))
    )
    (net (code "58") (name "unconnected-(USB-NC2-Pad7)") (class "Default")
      (node (ref "USB") (pin "7") (pinfunction "NC2_7") (pintype "bidirectional"))
    )
    (net (code "59") (name "unconnected-(WIFI-Pad3)") (class "Default")
      (node (ref "WIFI") (pin "3") (pinfunction "3_3") (pintype "passive"))
    )
    (net (code "60") (name "unconnected-(WIFI-Pad4)") (class "Default")
      (node (ref "WIFI") (pin "4") (pinfunction "4_4") (pintype "passive"))
    )
    (net (code "61") (name "unconnected-(WIFI-Pad5)") (class "Default")
      (node (ref "WIFI") (pin "5") (pinfunction "5_5") (pintype "passive"))
    )
    (net (code "62") (name "unconnected-(WIFI-Pad6)") (class "Default")
      (node (ref "WIFI") (pin "6") (pinfunction "6_6") (pintype "passive"))
    )
  )
)
